# RF.net
KiCad netlist of a schematic drawn in Altium Designer
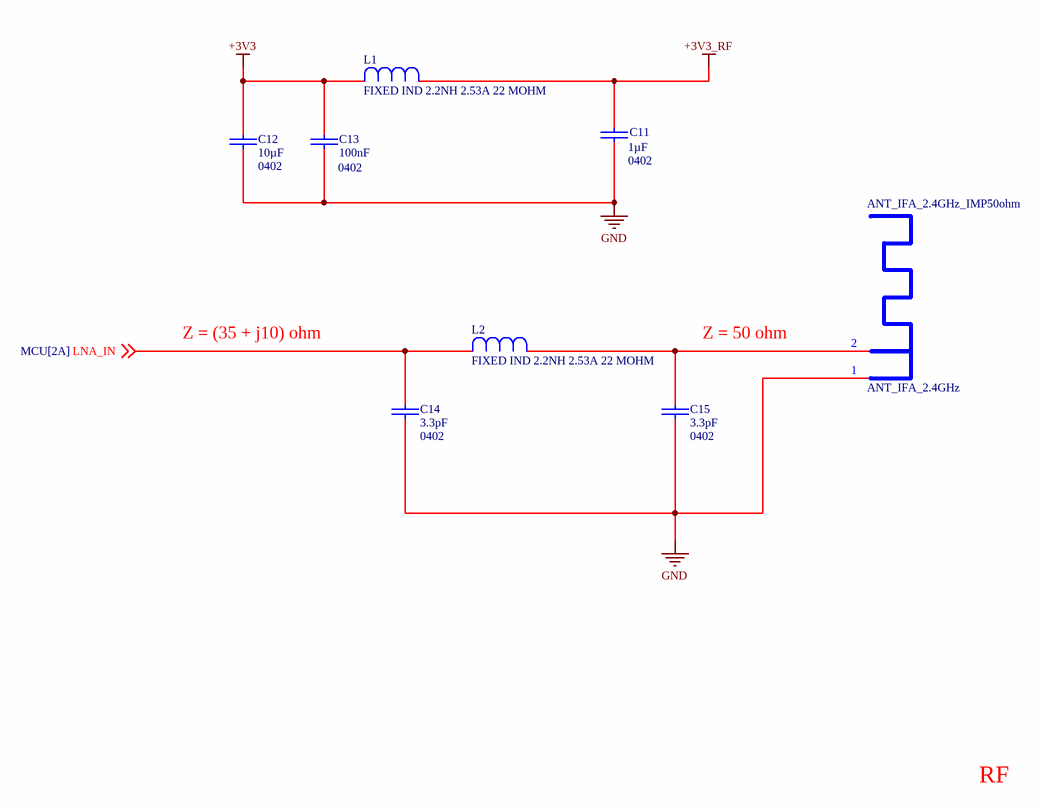
[diagram p0: RF.SchDoc]

(export (version "E")
  (design (tool "Eeschema 10.0.6"))
  (components
    (comp (ref "ANT_IFA_2.4GHz_IMP50ohm")
      (value "ANT_IFA_2.4GHz")
      (footprint "ANT_IFA_2.4GHz")
      (libsource (lib "Schlib") (part "ANT_IFA_2.4GHz"))
    )
    (comp (ref "C11")
      (value "1µF")
      (footprint "C0402")
      (description "Multilayer Ceramic Capacitors MLCC – SMD/SMT; YAGEO; CC0402KRX5R6BB105; 1 µF; 0402; 10 V; 10 V")
      (fields
        (field (name "MANUFACTURER") "Yageo Group")
        (field (name "MANUFACTURER PART NUMBER") "CC0402KRX5R6BB105")
        (field (name "CASE/PACKAGE") "0402")
      )
      (libsource (lib "Schlib") (part "CC0402KRX5R6BB105"))
    )
    (comp (ref "C12")
      (value "10µF")
      (footprint "C0402")
      (description "10V 10uF X5R ±20% 0402 Multilayer Ceramic Capacitors MLCC - SMD/SMT ROHS")
      (fields
        (field (name "MANUFACTURER") "Murata")
        (field (name "MANUFACTURER PART NUMBER") "GRM155R61A106ME11D")
        (field (name "CASE/PACKAGE") "0402")
      )
      (libsource (lib "Schlib") (part "GRM155R61A106ME11D"))
    )
    (comp (ref "C13")
      (value "100nF")
      (footprint "C0402")
      (description "50V 100nF X5R ±10% 0402 Multilayer Ceramic Capacitors MLCC - SMD/SMT ROHS")
      (fields
        (field (name "MANUFACTURER") "Yageo Group")
        (field (name "MANUFACTURER PART NUMBER") "CC0402KRX5R9BB104")
        (field (name "CASE/PACKAGE") "0402")
      )
      (libsource (lib "Schlib") (part "CC0402KRX5R9BB104"))
    )
    (comp (ref "C14")
      (value "3.3pF")
      (footprint "C0402")
      (description "Cap Ceramic 3.3pF 100V C0G 0.25pF Pad SMD 0402 125C T/R")
      (fields
        (field (name "MANUFACTURER") "Murata")
        (field (name "MANUFACTURER PART NUMBER") "GRM1555C2A3R3CA01D")
        (field (name "CASE/PACKAGE") "0402")
      )
      (libsource (lib "Schlib") (part "GRM1555C2A3R3CA01D"))
    )
    (comp (ref "C15")
      (value "3.3pF")
      (footprint "C0402")
      (description "Cap Ceramic 3.3pF 100V C0G 0.25pF Pad SMD 0402 125C T/R")
      (fields
        (field (name "MANUFACTURER") "Murata")
        (field (name "MANUFACTURER PART NUMBER") "GRM1555C2A3R3CA01D")
        (field (name "CASE/PACKAGE") "0402")
      )
      (libsource (lib "Schlib") (part "GRM1555C2A3R3CA01D"))
    )
    (comp (ref "L1")
      (value "FIXED IND 2.2NH 2.53A 22 MOHM")
      (footprint "INDC1006X60N")
      (description "General Purpose Inductor, 0.0022uH, 2%, 1 Element, Wirewound-Core, Reflow soldering, 1005/0402")
      (fields
        (field (name "MANUFACTURER") "Murata")
        (field (name "MANUFACTURER PART NUMBER") "LQW15AN2N2G80D")
      )
      (libsource (lib "Schlib") (part "LQW15AN2N2G80D"))
    )
    (comp (ref "L2")
      (value "FIXED IND 2.2NH 2.53A 22 MOHM")
      (footprint "INDC1006X60N")
      (description "General Purpose Inductor, 0.0022uH, 2%, 1 Element, Wirewound-Core, Reflow soldering, 1005/0402")
      (fields
        (field (name "MANUFACTURER") "Murata")
        (field (name "MANUFACTURER PART NUMBER") "LQW15AN2N2G80D")
      )
      (libsource (lib "Schlib") (part "LQW15AN2N2G80D"))
    )
  )
  (nets
    (net (code "1") (name "+3V3") (class "Default")
      (node (ref "C12") (pin "2") (pinfunction "2_2") (pintype "passive"))
      (node (ref "C13") (pin "2") (pinfunction "2_2") (pintype "passive"))
      (node (ref "L1") (pin "2") (pinfunction "2_2") (pintype "passive"))
    )
    (net (code "2") (name "+3V3_RF") (class "Default")
      (node (ref "C11") (pin "2") (pinfunction "2_2") (pintype "passive"))
      (node (ref "L1") (pin "1") (pinfunction "1_1") (pintype "passive"))
    )
    (net (code "3") (name "GND") (class "Default")
      (node (ref "ANT_IFA_2.4GHz_IMP50ohm") (pin "1") (pinfunction "1_1") (pintype "passive"))
      (node (ref "C11") (pin "1") (pinfunction "1_1") (pintype "passive"))
      (node (ref "C12") (pin "1") (pinfunction "1_1") (pintype "passive"))
      (node (ref "C13") (pin "1") (pinfunction "1_1") (pintype "passive"))
      (node (ref "C14") (pin "1") (pinfunction "1_1") (pintype "passive"))
      (node (ref "C15") (pin "1") (pinfunction "1_1") (pintype "passive"))
    )
    (net (code "4") (name "LNA_IN") (class "Default")
      (node (ref "C14") (pin "2") (pinfunction "2_2") (pintype "passive"))
      (node (ref "L2") (pin "2") (pinfunction "2_2") (pintype "passive"))
    )
    (net (code "5") (name "Net-(ANT_IFA_2.4GHz_IMP50ohm-Pad2)") (class "Default")
      (node (ref "ANT_IFA_2.4GHz_IMP50ohm") (pin "2") (pinfunction "2_2") (pintype "passive"))
      (node (ref "C15") (pin "2") (pinfunction "2_2") (pintype "passive"))
      (node (ref "L2") (pin "1") (pinfunction "1_1") (pintype "passive"))
    )
  )
)
